# FMC_130MSPS_4CH.net
KiCad netlist of a schematic drawn in Altium Designer
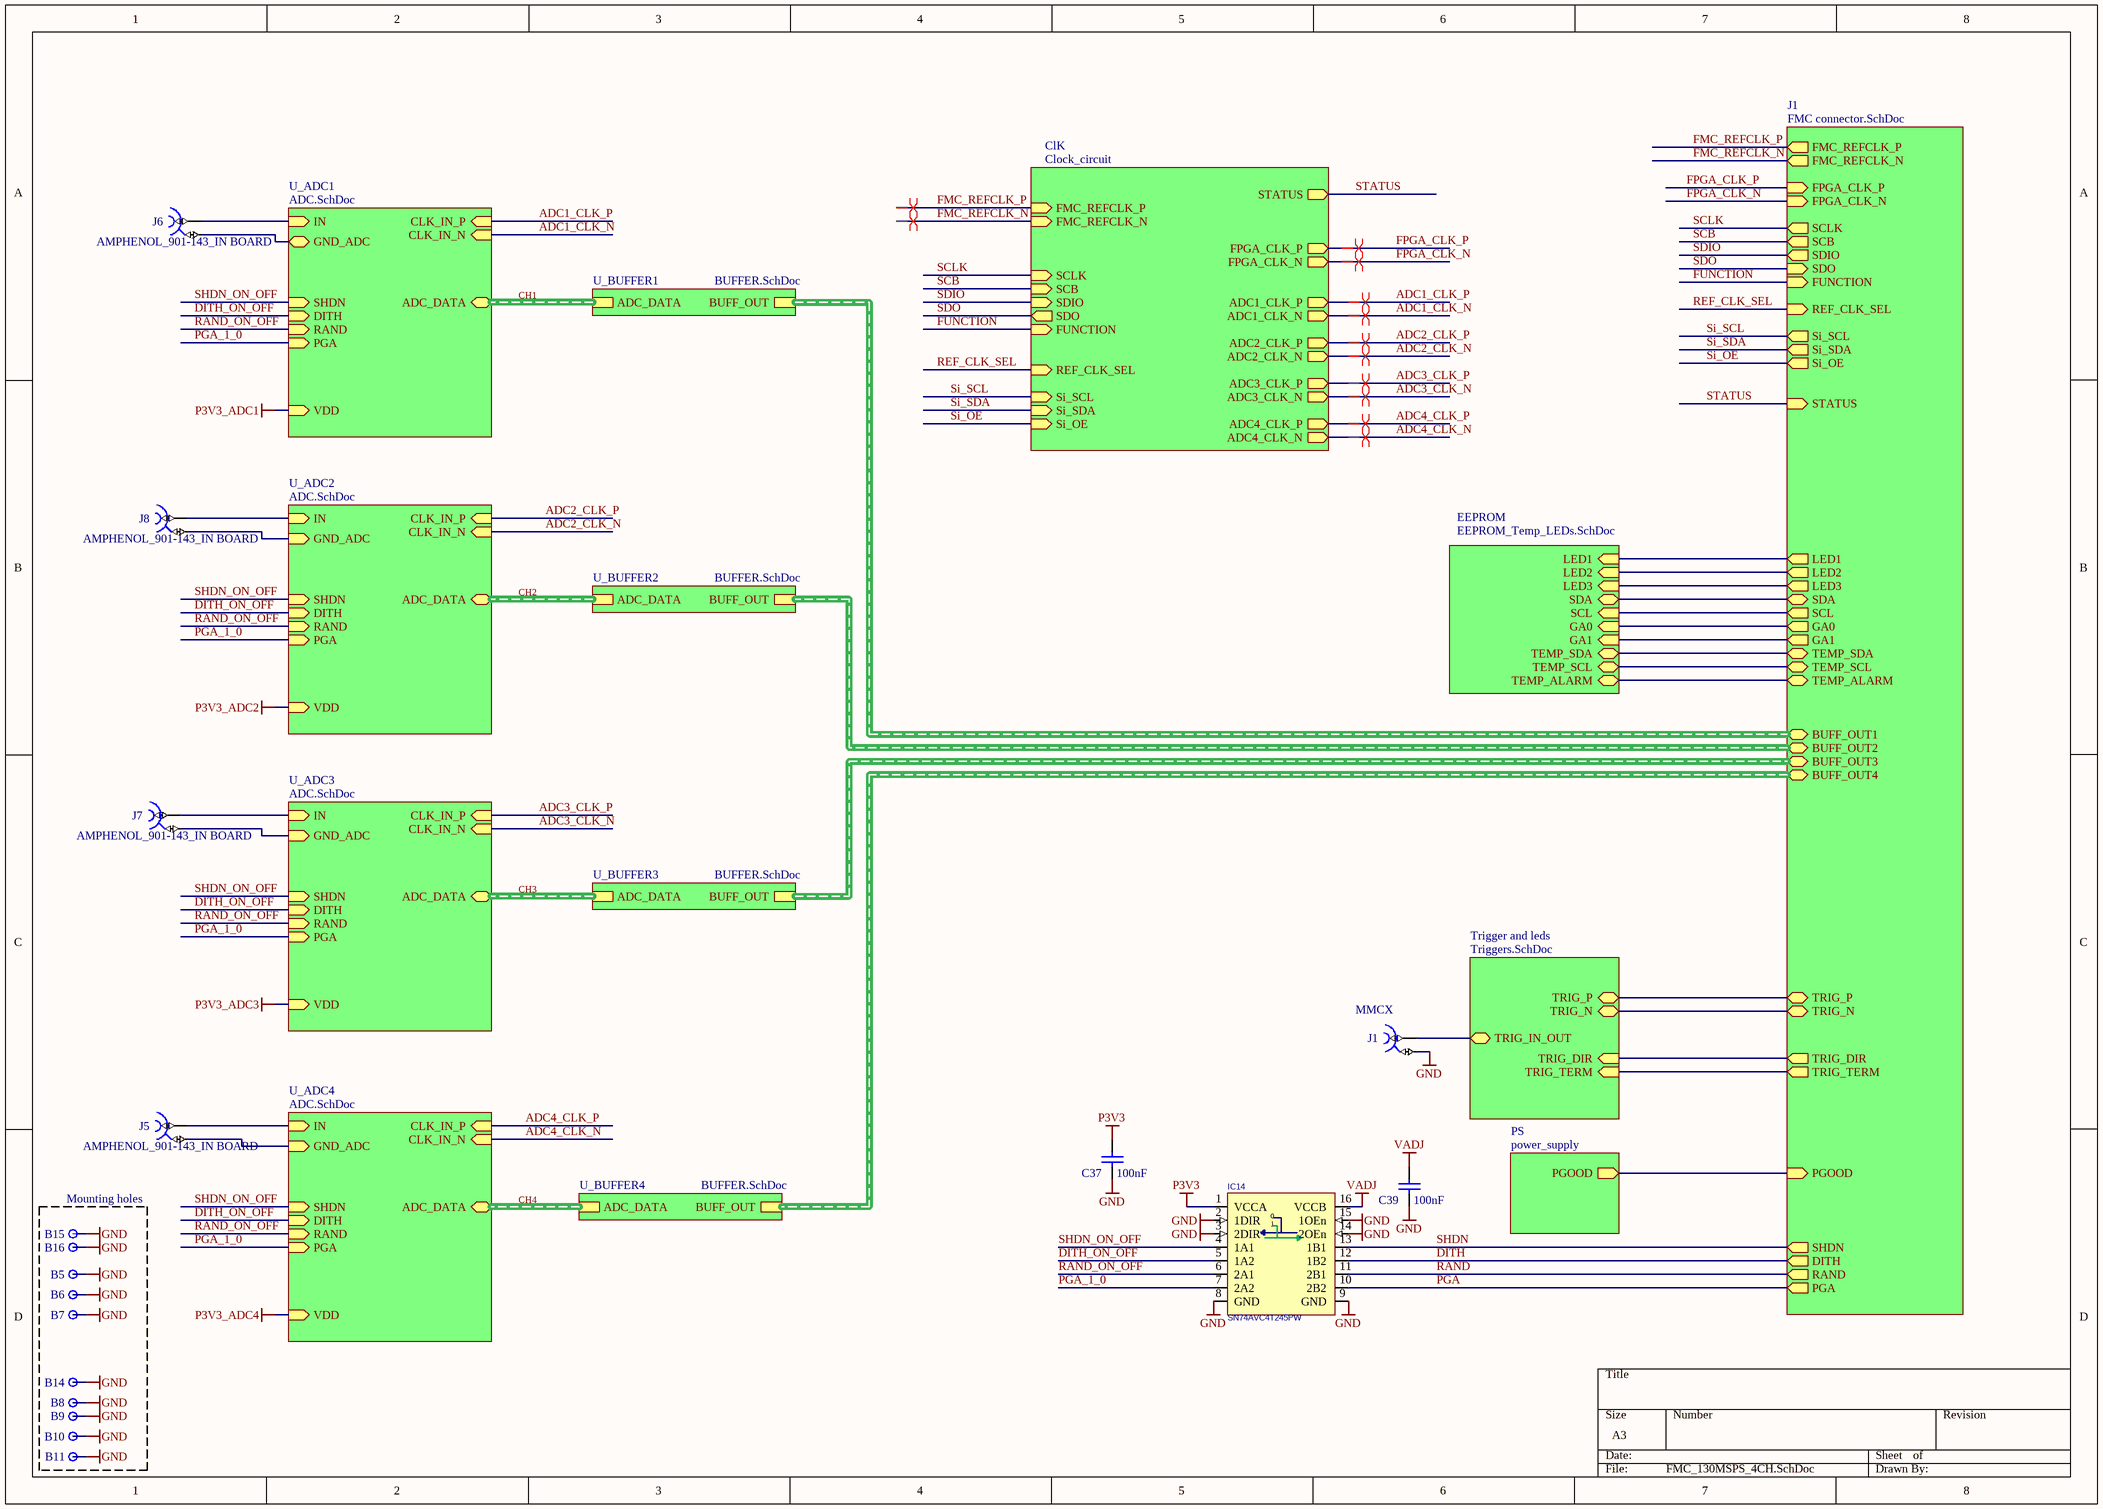
[diagram p0: FMC_130MSPS_4CH.SchDoc]

(export (version "E")
  (design (tool "Eeschema 10.0.6"))
  (components
    (comp (ref "B5")
      (value "Plated Hole")
      (footprint "MTG240_400")
      (description "Single Terminal Socket")
      (fields (field (name "PART NUMBER") "PLATED_HOLE2.4_PAD4.0") (field (name "AUTHOR") "CERN DEM JMW"))
      (libsource (lib "Eletro-mechanical") (part "Single Terminal Socket"))
    )
    (comp (ref "B6")
      (value "Plated Hole")
      (footprint "MTG240_400")
      (description "Single Terminal Socket")
      (fields (field (name "PART NUMBER") "PLATED_HOLE2.4_PAD4.0") (field (name "AUTHOR") "CERN DEM JMW"))
      (libsource (lib "Eletro-mechanical") (part "Single Terminal Socket"))
    )
    (comp (ref "B7")
      (value "Plated Hole")
      (footprint "MTG240_400")
      (description "Single Terminal Socket")
      (fields (field (name "PART NUMBER") "PLATED_HOLE2.4_PAD4.0") (field (name "AUTHOR") "CERN DEM JMW"))
      (libsource (lib "Eletro-mechanical") (part "Single Terminal Socket"))
    )
    (comp (ref "B8")
      (value "Plated Hole")
      (footprint "MTG240_400")
      (description "Single Terminal Socket")
      (fields (field (name "PART NUMBER") "PLATED_HOLE2.4_PAD4.0") (field (name "AUTHOR") "CERN DEM JMW"))
      (libsource (lib "Eletro-mechanical") (part "Single Terminal Socket"))
    )
    (comp (ref "B9")
      (value "Plated Hole")
      (footprint "MTG240_400")
      (description "Single Terminal Socket")
      (fields (field (name "PART NUMBER") "PLATED_HOLE2.4_PAD4.0") (field (name "AUTHOR") "CERN DEM JMW"))
      (libsource (lib "Eletro-mechanical") (part "Single Terminal Socket"))
    )
    (comp (ref "B10")
      (value "Plated Hole")
      (footprint "MTG240_400")
      (description "Single Terminal Socket")
      (fields (field (name "PART NUMBER") "PLATED_HOLE2.4_PAD4.0") (field (name "AUTHOR") "CERN DEM JMW"))
      (libsource (lib "Eletro-mechanical") (part "Single Terminal Socket"))
    )
    (comp (ref "B11")
      (value "Plated Hole")
      (footprint "MTG240_400")
      (description "Single Terminal Socket")
      (fields (field (name "PART NUMBER") "PLATED_HOLE2.4_PAD4.0") (field (name "AUTHOR") "CERN DEM JMW"))
      (libsource (lib "Eletro-mechanical") (part "Single Terminal Socket"))
    )
    (comp (ref "B14")
      (value "Plated Hole")
      (footprint "MTG240_400")
      (description "Single Terminal Socket")
      (fields (field (name "PART NUMBER") "PLATED_HOLE2.4_PAD4.0") (field (name "AUTHOR") "CERN DEM JMW"))
      (libsource (lib "Eletro-mechanical") (part "Single Terminal Socket"))
    )
    (comp (ref "B15")
      (value "Plated Hole")
      (footprint "MTG240_400")
      (description "Single Terminal Socket")
      (fields (field (name "PART NUMBER") "PLATED_HOLE2.4_PAD4.0") (field (name "AUTHOR") "CERN DEM JMW"))
      (libsource (lib "Eletro-mechanical") (part "Single Terminal Socket"))
    )
    (comp (ref "B16")
      (value "Plated Hole")
      (footprint "MTG240_400")
      (description "Single Terminal Socket")
      (fields (field (name "PART NUMBER") "PLATED_HOLE2.4_PAD4.0") (field (name "AUTHOR") "CERN DEM JMW"))
      (libsource (lib "Eletro-mechanical") (part "Single Terminal Socket"))
    )
    (comp (ref "C37")
      (value "100nF")
      (footprint "CAPC0603X33N")
      (description "Non-polarised capacitor")
      (fields
        (field (name "PART NUMBER") "CC0201_100NF_6.3V_10%_X5R")
        (field (name "VOLTAGE") "6.3V")
        (field (name "AUTHOR") "CERN DEM JLC")
      )
      (libsource (lib "Capacitors") (part "Capacitor - non polarized"))
    )
    (comp (ref "C39")
      (value "100nF")
      (footprint "CAPC0603X33N")
      (description "Non-polarised capacitor")
      (fields
        (field (name "PART NUMBER") "CC0201_100NF_6.3V_10%_X5R")
        (field (name "VOLTAGE") "6.3V")
        (field (name "AUTHOR") "CERN DEM JLC")
      )
      (libsource (lib "Capacitors") (part "Capacitor - non polarized"))
    )
    (comp (ref "IC14")
      (value "SN74AVC4T245PW")
      (description "4-BIT DUAL-SUPPLY BUS TRANSCEIVER")
      (libsource (lib "LIBRARY_SCH") (part "74AVC4T245"))
    )
    (comp (ref "J1")
      (value "Coax_1Female_1Shield")
      (footprint "HUBER-SUHNER_85_MMCX-50-0-1/111 OH")
      (fields
        (field (name "PART NUMBER") "HUBER-SUHNER_85_MMCX-50-0-1/111 OH")
        (field (name "FAMILY") "MMCX")
        (field (name "MANUFACTURER") "HUBER+SUHNER")
        (field (name "MANUFACTURER PART NUMBER") "85_MMCX-50-0-1/111 OH")
        (field (name "AUTHOR") "CERN DEM JLC")
      )
      (libsource (lib "Connectors") (part "Coax_1Female_1Shield"))
    )
    (comp (ref "J5")
      (value "AMPHENOL_901-143_IN BOARD")
      (footprint "AMPHENOL_901-143_IN BOARD")
      (libsource (lib "Especial_DIG_Components") (part "AMPHENOL_901-143_IN BOARD"))
    )
    (comp (ref "J6")
      (value "AMPHENOL_901-143_IN BOARD")
      (footprint "AMPHENOL_901-143_IN BOARD")
      (libsource (lib "Especial_DIG_Components") (part "AMPHENOL_901-143_IN BOARD"))
    )
    (comp (ref "J7")
      (value "AMPHENOL_901-143_IN BOARD")
      (footprint "AMPHENOL_901-143_IN BOARD")
      (libsource (lib "Especial_DIG_Components") (part "AMPHENOL_901-143_IN BOARD"))
    )
    (comp (ref "J8")
      (value "AMPHENOL_901-143_IN BOARD")
      (footprint "AMPHENOL_901-143_IN BOARD")
      (libsource (lib "Especial_DIG_Components") (part "AMPHENOL_901-143_IN BOARD"))
    )
  )
  (nets
    (net (code "17") (name "/DITH") (class "Default")
      (node (ref "IC14") (pin "12") (pinfunction "1B2_12") (pintype "bidirectional"))
    )
    (net (code "18") (name "/DITH_ON_OFF") (class "Default")
      (node (ref "IC14") (pin "5") (pinfunction "1A2_5") (pintype "bidirectional"))
    )
    (net (code "26") (name "/GND_ADC") (class "Default")
      (node (ref "J8") (pin "2") (pinfunction "2_2") (pintype "bidirectional"))
    )
    (net (code "27") (name "/GND_ADC_1") (class "Default")
      (node (ref "J5") (pin "2") (pinfunction "2_2") (pintype "bidirectional"))
    )
    (net (code "28") (name "/GND_ADC_2") (class "Default")
      (node (ref "J7") (pin "2") (pinfunction "2_2") (pintype "bidirectional"))
    )
    (net (code "29") (name "/GND_ADC_3") (class "Default")
      (node (ref "J6") (pin "2") (pinfunction "2_2") (pintype "bidirectional"))
    )
    (net (code "30") (name "/IN") (class "Default")
      (node (ref "J8") (pin "1") (pinfunction "1_1") (pintype "bidirectional"))
    )
    (net (code "31") (name "/IN_1") (class "Default")
      (node (ref "J5") (pin "1") (pinfunction "1_1") (pintype "bidirectional"))
    )
    (net (code "32") (name "/IN_2") (class "Default")
      (node (ref "J7") (pin "1") (pinfunction "1_1") (pintype "bidirectional"))
    )
    (net (code "33") (name "/IN_3") (class "Default")
      (node (ref "J6") (pin "1") (pinfunction "1_1") (pintype "bidirectional"))
    )
    (net (code "37") (name "/PGA") (class "Default")
      (node (ref "IC14") (pin "10") (pinfunction "2B2_10") (pintype "bidirectional"))
    )
    (net (code "38") (name "/PGA_1_0") (class "Default")
      (node (ref "IC14") (pin "7") (pinfunction "2A2_7") (pintype "bidirectional"))
    )
    (net (code "40") (name "/RAND") (class "Default")
      (node (ref "IC14") (pin "11") (pinfunction "2B1_11") (pintype "bidirectional"))
    )
    (net (code "41") (name "/RAND_ON_OFF") (class "Default")
      (node (ref "IC14") (pin "6") (pinfunction "2A1_6") (pintype "bidirectional"))
    )
    (net (code "49") (name "/SHDN") (class "Default")
      (node (ref "IC14") (pin "13") (pinfunction "1B1_13") (pintype "bidirectional"))
    )
    (net (code "50") (name "/SHDN_ON_OFF") (class "Default")
      (node (ref "IC14") (pin "4") (pinfunction "1A1_4") (pintype "bidirectional"))
    )
    (net (code "59") (name "/TRIG_IN_OUT") (class "Default")
      (node (ref "J1") (pin "1") (pinfunction "1_1") (pintype "bidirectional"))
    )
    (net (code "67") (name "GND") (class "Default")
      (node (ref "B10") (pin "1") (pinfunction "1_1") (pintype "passive"))
      (node (ref "B11") (pin "1") (pinfunction "1_1") (pintype "passive"))
      (node (ref "B14") (pin "1") (pinfunction "1_1") (pintype "passive"))
      (node (ref "B15") (pin "1") (pinfunction "1_1") (pintype "passive"))
      (node (ref "B16") (pin "1") (pinfunction "1_1") (pintype "passive"))
      (node (ref "B5") (pin "1") (pinfunction "1_1") (pintype "passive"))
      (node (ref "B6") (pin "1") (pinfunction "1_1") (pintype "passive"))
      (node (ref "B7") (pin "1") (pinfunction "1_1") (pintype "passive"))
      (node (ref "B8") (pin "1") (pinfunction "1_1") (pintype "passive"))
      (node (ref "B9") (pin "1") (pinfunction "1_1") (pintype "passive"))
      (node (ref "C37") (pin "1") (pinfunction "1_1") (pintype "passive"))
      (node (ref "C39") (pin "1") (pinfunction "1_1") (pintype "passive"))
      (node (ref "IC14") (pin "14") (pinfunction "2OEn_14") (pintype "input"))
      (node (ref "IC14") (pin "15") (pinfunction "1OEn_15") (pintype "input"))
      (node (ref "IC14") (pin "2") (pinfunction "1DIR_2") (pintype "input"))
      (node (ref "IC14") (pin "3") (pinfunction "2DIR_3") (pintype "input"))
      (node (ref "IC14") (pin "8") (pinfunction "GND_8") (pintype "power_in"))
      (node (ref "IC14") (pin "9") (pinfunction "GND_9") (pintype "power_in"))
      (node (ref "J1") (pin "2") (pinfunction "2_2") (pintype "bidirectional"))
    )
    (net (code "68") (name "P3V3") (class "Default")
      (node (ref "C37") (pin "2") (pinfunction "2_2") (pintype "passive"))
      (node (ref "IC14") (pin "1") (pinfunction "VCCA_1") (pintype "power_in"))
    )
    (net (code "73") (name "VADJ") (class "Default")
      (node (ref "C39") (pin "2") (pinfunction "2_2") (pintype "passive"))
      (node (ref "IC14") (pin "16") (pinfunction "VCCB_16") (pintype "power_in"))
    )
  )
)
